# TSAL_logic_TNN_V1_0.net
KiCad netlist of a schematic drawn in EAGLE
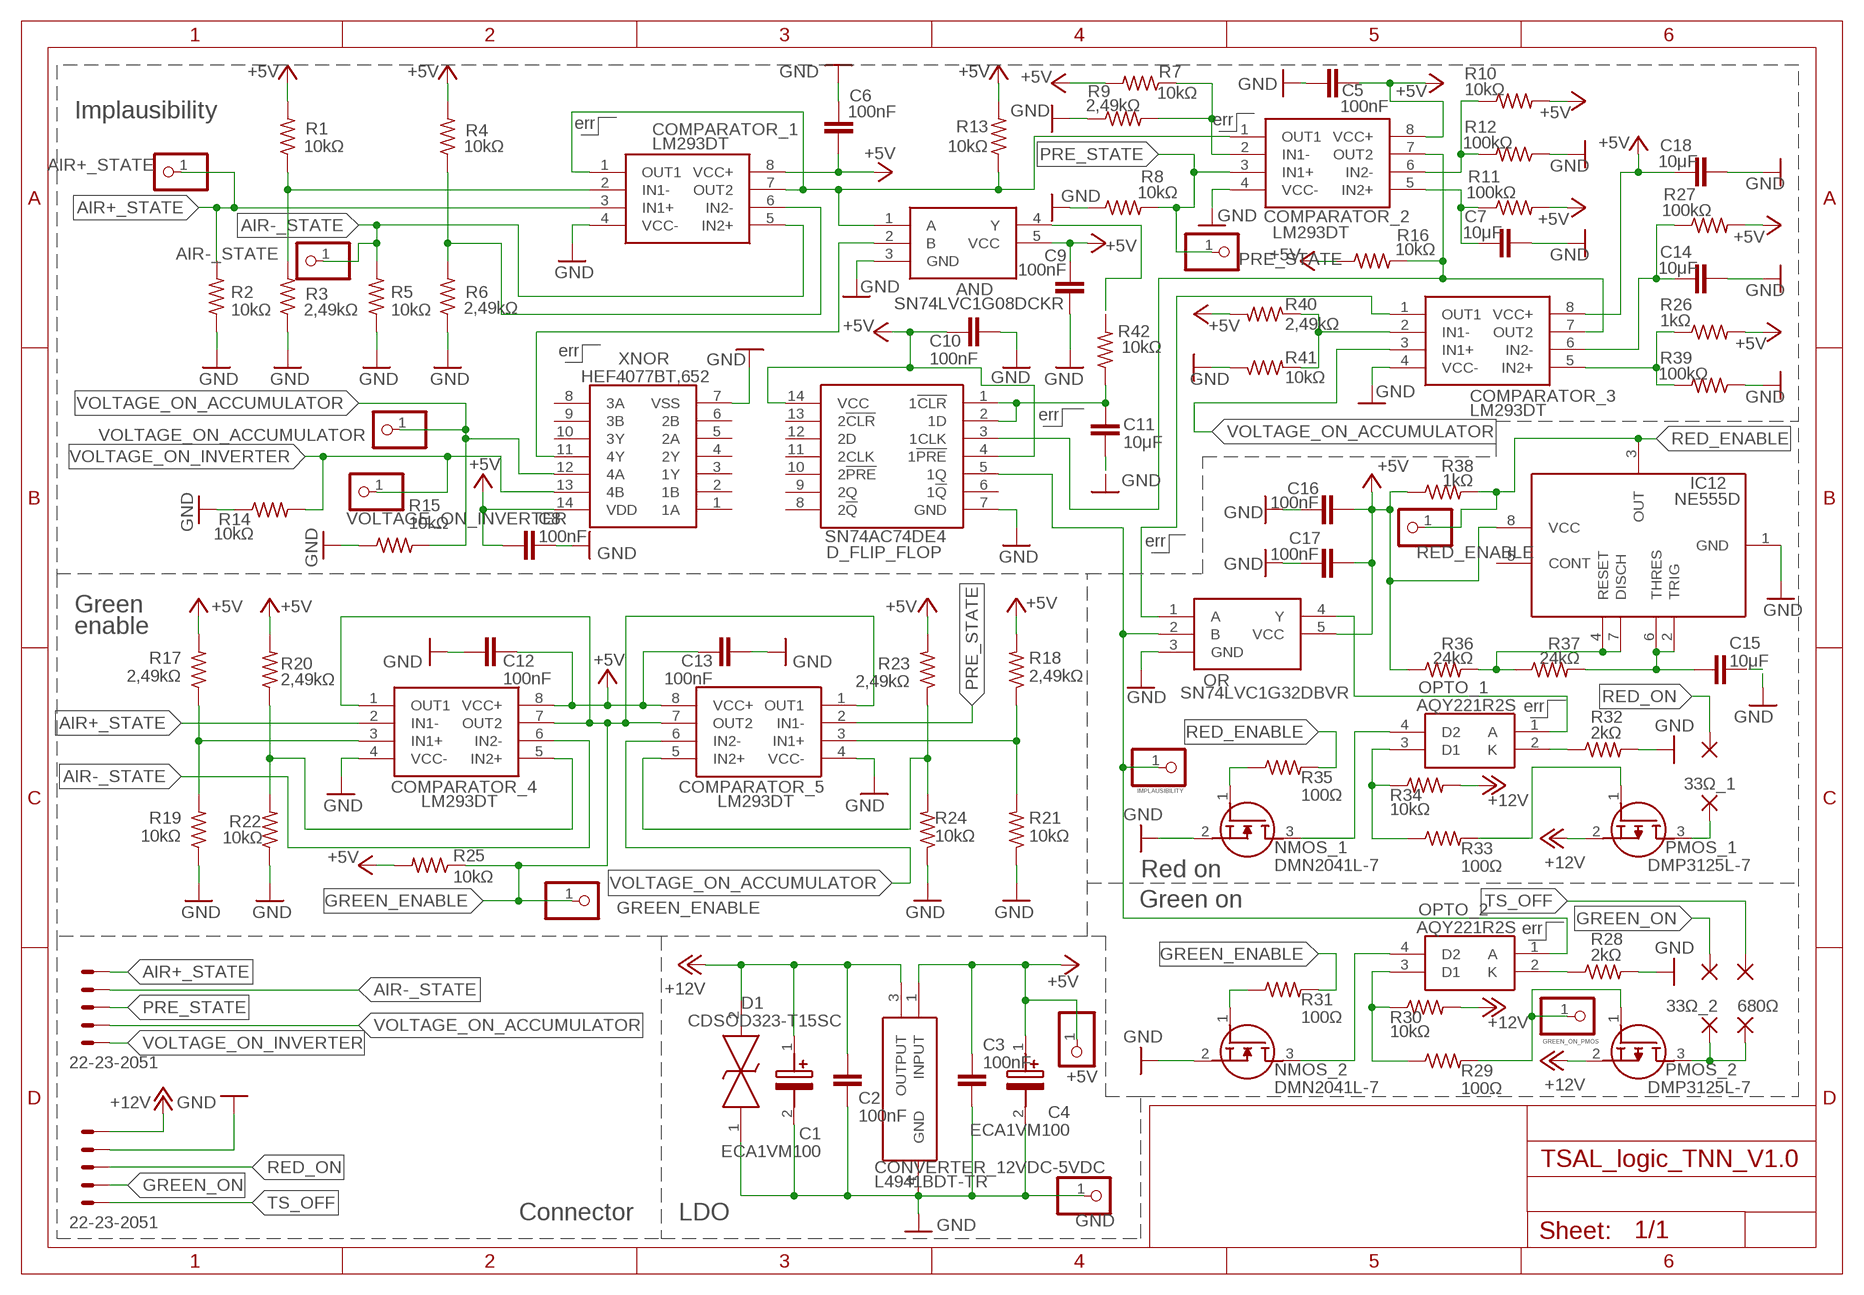
[diagram p0: schematic, sheet 1]

(export (version "E")
  (design (tool "Eeschema 10.0.6"))
  (components
    (comp (ref "+5V")
      (value "PINHD-1X1")
      (footprint "eagle-import:1X01")
      (libsource (lib "eagle-import") (part "PINHD-1X1"))
    )
    (comp (ref "33Ω_1")
      (value "1,6/0,8")
      (footprint "eagle-import:1,6_0,8")
      (libsource (lib "eagle-import") (part "1,6/0,8"))
    )
    (comp (ref "33Ω_1_")
      (value "1,6/0,8")
      (footprint "eagle-import:1,6_0,8")
      (libsource (lib "eagle-import") (part "1,6/0,8"))
    )
    (comp (ref "33Ω_2")
      (value "1,6/0,8")
      (footprint "eagle-import:1,6_0,8")
      (libsource (lib "eagle-import") (part "1,6/0,8"))
    )
    (comp (ref "33Ω_2_")
      (value "1,6/0,8")
      (footprint "eagle-import:1,6_0,8")
      (libsource (lib "eagle-import") (part "1,6/0,8"))
    )
    (comp (ref "680Ω")
      (value "1,6/0,8")
      (footprint "eagle-import:1,6_0,8")
      (libsource (lib "eagle-import") (part "1,6/0,8"))
    )
    (comp (ref "680Ω_")
      (value "1,6/0,8")
      (footprint "eagle-import:1,6_0,8")
      (libsource (lib "eagle-import") (part "1,6/0,8"))
    )
    (comp (ref "AIR+_STATE")
      (value "PINHD-1X1")
      (footprint "eagle-import:1X01")
      (libsource (lib "eagle-import") (part "PINHD-1X1"))
    )
    (comp (ref "AIR-_STATE")
      (value "PINHD-1X1")
      (footprint "eagle-import:1X01")
      (libsource (lib "eagle-import") (part "PINHD-1X1"))
    )
    (comp (ref "AND")
      (value "SN74LVC1G08DCKR")
      (footprint "eagle-import:SOT65P210X110-5N")
      (fields (field (name "MOUSER_PART_NUMBER") "595-SN74LVC1G08DCKR"))
      (libsource (lib "eagle-import") (part "SN74LVC1G08DCKR"))
    )
    (comp (ref "C1")
      (value "ECA1VM100")
      (footprint "eagle-import:CAPPRD200W55D525H1200")
      (libsource (lib "eagle-import") (part "ECA1VM100"))
    )
    (comp (ref "C2")
      (value "100nF")
      (footprint "eagle-import:C0603")
      (libsource (lib "eagle-import") (part "C-EUC0603"))
    )
    (comp (ref "C3")
      (value "100nF")
      (footprint "eagle-import:C0603")
      (libsource (lib "eagle-import") (part "C-EUC0603"))
    )
    (comp (ref "C4")
      (value "ECA1VM100")
      (footprint "eagle-import:CAPPRD200W55D525H1200")
      (libsource (lib "eagle-import") (part "ECA1VM100"))
    )
    (comp (ref "C5")
      (value "100nF")
      (footprint "eagle-import:C0603")
      (libsource (lib "eagle-import") (part "C-EUC0603"))
    )
    (comp (ref "C6")
      (value "100nF")
      (footprint "eagle-import:C0603")
      (libsource (lib "eagle-import") (part "C-EUC0603"))
    )
    (comp (ref "C7")
      (value "10μF")
      (footprint "eagle-import:C0603")
      (libsource (lib "eagle-import") (part "C-EUC0603"))
    )
    (comp (ref "C8")
      (value "100nF")
      (footprint "eagle-import:C0603")
      (libsource (lib "eagle-import") (part "C-EUC0603"))
    )
    (comp (ref "C9")
      (value "100nF")
      (footprint "eagle-import:C0603")
      (libsource (lib "eagle-import") (part "C-EUC0603"))
    )
    (comp (ref "C10")
      (value "100nF")
      (footprint "eagle-import:C0603")
      (libsource (lib "eagle-import") (part "C-EUC0603"))
    )
    (comp (ref "C11")
      (value "10μF")
      (footprint "eagle-import:C0603")
      (libsource (lib "eagle-import") (part "C-EUC0603"))
    )
    (comp (ref "C12")
      (value "100nF")
      (footprint "eagle-import:C0603")
      (libsource (lib "eagle-import") (part "C-EUC0603"))
    )
    (comp (ref "C13")
      (value "100nF")
      (footprint "eagle-import:C0603")
      (libsource (lib "eagle-import") (part "C-EUC0603"))
    )
    (comp (ref "C14")
      (value "10μF")
      (footprint "eagle-import:C0603")
      (libsource (lib "eagle-import") (part "C-EUC0603"))
    )
    (comp (ref "C15")
      (value "10μF")
      (footprint "eagle-import:C0603")
      (libsource (lib "eagle-import") (part "C-EUC0603"))
    )
    (comp (ref "C16")
      (value "100nF")
      (footprint "eagle-import:C0603")
      (libsource (lib "eagle-import") (part "C-EUC0603"))
    )
    (comp (ref "C17")
      (value "100nF")
      (footprint "eagle-import:C0603")
      (libsource (lib "eagle-import") (part "C-EUC0603"))
    )
    (comp (ref "C18")
      (value "10μF")
      (footprint "eagle-import:C0603")
      (libsource (lib "eagle-import") (part "C-EUC0603"))
    )
    (comp (ref "COMPARATOR_1")
      (value "LM293DT")
      (footprint "eagle-import:SOIC127P600X175-8N")
      (fields (field (name "MOUSER_PART_NUMBER") "511-LM293DT"))
      (libsource (lib "eagle-import") (part "LM293DT"))
    )
    (comp (ref "COMPARATOR_2")
      (value "LM293DT")
      (footprint "eagle-import:SOIC127P600X175-8N")
      (fields (field (name "MOUSER_PART_NUMBER") "511-LM293DT"))
      (libsource (lib "eagle-import") (part "LM293DT"))
    )
    (comp (ref "COMPARATOR_3")
      (value "LM293DT")
      (footprint "eagle-import:SOIC127P600X175-8N")
      (fields (field (name "MOUSER_PART_NUMBER") "511-LM293DT"))
      (libsource (lib "eagle-import") (part "LM293DT"))
    )
    (comp (ref "COMPARATOR_4")
      (value "LM293DT")
      (footprint "eagle-import:SOIC127P600X175-8N")
      (fields (field (name "MOUSER_PART_NUMBER") "511-LM293DT"))
      (libsource (lib "eagle-import") (part "LM293DT"))
    )
    (comp (ref "COMPARATOR_5")
      (value "LM293DT")
      (footprint "eagle-import:SOIC127P600X175-8N")
      (fields (field (name "MOUSER_PART_NUMBER") "511-LM293DT"))
      (libsource (lib "eagle-import") (part "LM293DT"))
    )
    (comp (ref "CONTACTOR_STATE_AND_VOLTAGE_MEASUREMENT")
      (value "22-23-2051")
      (footprint "eagle-import:22-23-2051")
      (fields (field (name "MF") "MOLEX"))
      (libsource (lib "eagle-import") (part "22-23-2051"))
    )
    (comp (ref "CONVERTER_12VDC-5VDC")
      (value "L4941BDT-TR")
      (footprint "eagle-import:TO228P972X240-3N")
      (fields (field (name "MOUSER_PART_NUMBER") "511-L4941BDT-TR"))
      (libsource (lib "eagle-import") (part "L4941BDT-TR"))
    )
    (comp (ref "D1")
      (value "CDSOD323-T15SC")
      (footprint "eagle-import:SOD-323")
      (fields (field (name "MOUSER_PART_NUMBER") "652-CDSOD323-T15SC"))
      (libsource (lib "eagle-import") (part "CDSOD323-T15SC"))
    )
    (comp (ref "D_FLIP_FLOP")
      (value "SN74AC74DE4")
      (footprint "eagle-import:SOIC127P600X175-14N")
      (fields (field (name "MOUSER_PART_NUMBER") "595-SN74AC74DE4"))
      (libsource (lib "eagle-import") (part "SN74AC74DE4"))
    )
    (comp (ref "GND")
      (value "PINHD-1X1")
      (footprint "eagle-import:1X01")
      (libsource (lib "eagle-import") (part "PINHD-1X1"))
    )
    (comp (ref "GREEN_ENABLE")
      (value "PINHD-1X1")
      (footprint "eagle-import:1X01")
      (libsource (lib "eagle-import") (part "PINHD-1X1"))
    )
    (comp (ref "GREEN_ON_PMOS")
      (value "PINHD-1X1")
      (footprint "eagle-import:1X01")
      (libsource (lib "eagle-import") (part "PINHD-1X1"))
    )
    (comp (ref "IC12")
      (value "NE555D")
      (footprint "eagle-import:SOIC127P600X175-8N")
      (fields (field (name "MOUSER_PART_NUMBER") "595-NE555D"))
      (libsource (lib "eagle-import") (part "NE555D"))
    )
    (comp (ref "IMPLAUSIBILITY")
      (value "PINHD-1X1")
      (footprint "eagle-import:1X01")
      (libsource (lib "eagle-import") (part "PINHD-1X1"))
    )
    (comp (ref "NMOS_1")
      (value "DMN2041L-7")
      (footprint "eagle-import:SOT96P240X110-3N")
      (fields (field (name "MOUSER_PART_NUMBER") "621-DMN2041L-7"))
      (libsource (lib "eagle-import") (part "DMN2041L-7"))
    )
    (comp (ref "NMOS_2")
      (value "DMN2041L-7")
      (footprint "eagle-import:SOT96P240X110-3N")
      (fields (field (name "MOUSER_PART_NUMBER") "621-DMN2041L-7"))
      (libsource (lib "eagle-import") (part "DMN2041L-7"))
    )
    (comp (ref "OPTO_1")
      (value "AQY221R2S")
      (footprint "eagle-import:SOP254P680X230-4N")
      (fields (field (name "MOUSER_PART_NUMBER") "769-AQY221R2S"))
      (libsource (lib "eagle-import") (part "AQY221R2S"))
    )
    (comp (ref "OPTO_2")
      (value "AQY221R2S")
      (footprint "eagle-import:SOP254P680X230-4N")
      (fields (field (name "MOUSER_PART_NUMBER") "769-AQY221R2S"))
      (libsource (lib "eagle-import") (part "AQY221R2S"))
    )
    (comp (ref "OR")
      (value "SN74LVC1G32DBVR")
      (footprint "eagle-import:SOT95P280X145-5N")
      (fields (field (name "MOUSER_PART_NUMBER") "595-SN74LVC1G32DBVR"))
      (libsource (lib "eagle-import") (part "SN74LVC1G32DBVR"))
    )
    (comp (ref "PMOS_1")
      (value "DMP3125L-7")
      (footprint "eagle-import:SOT96P240X110-3N")
      (fields (field (name "MOUSER_PART_NUMBER") "621-DMP3125L-7"))
      (libsource (lib "eagle-import") (part "DMP3125L-7"))
    )
    (comp (ref "PMOS_2")
      (value "DMP3125L-7")
      (footprint "eagle-import:SOT96P240X110-3N")
      (fields (field (name "MOUSER_PART_NUMBER") "621-DMP3125L-7"))
      (libsource (lib "eagle-import") (part "DMP3125L-7"))
    )
    (comp (ref "PRE_STATE")
      (value "PINHD-1X1")
      (footprint "eagle-import:1X01")
      (libsource (lib "eagle-import") (part "PINHD-1X1"))
    )
    (comp (ref "R1")
      (value "10kΩ")
      (footprint "eagle-import:R0603")
      (libsource (lib "eagle-import") (part "R-US_R0603"))
    )
    (comp (ref "R2")
      (value "10kΩ")
      (footprint "eagle-import:R0603")
      (libsource (lib "eagle-import") (part "R-US_R0603"))
    )
    (comp (ref "R3")
      (value "2,49kΩ")
      (footprint "eagle-import:R0603")
      (libsource (lib "eagle-import") (part "R-US_R0603"))
    )
    (comp (ref "R4")
      (value "10kΩ")
      (footprint "eagle-import:R0603")
      (libsource (lib "eagle-import") (part "R-US_R0603"))
    )
    (comp (ref "R5")
      (value "10kΩ")
      (footprint "eagle-import:R0603")
      (libsource (lib "eagle-import") (part "R-US_R0603"))
    )
    (comp (ref "R6")
      (value "2,49kΩ")
      (footprint "eagle-import:R0603")
      (libsource (lib "eagle-import") (part "R-US_R0603"))
    )
    (comp (ref "R7")
      (value "10kΩ")
      (footprint "eagle-import:R0603")
      (libsource (lib "eagle-import") (part "R-US_R0603"))
    )
    (comp (ref "R8")
      (value "10kΩ")
      (footprint "eagle-import:R0603")
      (libsource (lib "eagle-import") (part "R-US_R0603"))
    )
    (comp (ref "R9")
      (value "2,49kΩ")
      (footprint "eagle-import:R0603")
      (libsource (lib "eagle-import") (part "R-US_R0603"))
    )
    (comp (ref "R10")
      (value "10kΩ")
      (footprint "eagle-import:R0603")
      (libsource (lib "eagle-import") (part "R-US_R0603"))
    )
    (comp (ref "R11")
      (value "100kΩ")
      (footprint "eagle-import:R0603")
      (libsource (lib "eagle-import") (part "R-US_R0603"))
    )
    (comp (ref "R12")
      (value "100kΩ")
      (footprint "eagle-import:R0603")
      (libsource (lib "eagle-import") (part "R-US_R0603"))
    )
    (comp (ref "R13")
      (value "10kΩ")
      (footprint "eagle-import:R0603")
      (libsource (lib "eagle-import") (part "R-US_R0603"))
    )
    (comp (ref "R14")
      (value "10kΩ")
      (footprint "eagle-import:R0603")
      (libsource (lib "eagle-import") (part "R-US_R0603"))
    )
    (comp (ref "R15")
      (value "10kΩ")
      (footprint "eagle-import:R0603")
      (libsource (lib "eagle-import") (part "R-US_R0603"))
    )
    (comp (ref "R16")
      (value "10kΩ")
      (footprint "eagle-import:R0603")
      (libsource (lib "eagle-import") (part "R-US_R0603"))
    )
    (comp (ref "R17")
      (value "2,49kΩ")
      (footprint "eagle-import:R0603")
      (libsource (lib "eagle-import") (part "R-US_R0603"))
    )
    (comp (ref "R18")
      (value "2,49kΩ")
      (footprint "eagle-import:R0603")
      (libsource (lib "eagle-import") (part "R-US_R0603"))
    )
    (comp (ref "R19")
      (value "10kΩ")
      (footprint "eagle-import:R0603")
      (libsource (lib "eagle-import") (part "R-US_R0603"))
    )
    (comp (ref "R20")
      (value "2,49kΩ")
      (footprint "eagle-import:R0603")
      (libsource (lib "eagle-import") (part "R-US_R0603"))
    )
    (comp (ref "R21")
      (value "10kΩ")
      (footprint "eagle-import:R0603")
      (libsource (lib "eagle-import") (part "R-US_R0603"))
    )
    (comp (ref "R22")
      (value "10kΩ")
      (footprint "eagle-import:R0603")
      (libsource (lib "eagle-import") (part "R-US_R0603"))
    )
    (comp (ref "R23")
      (value "2,49kΩ")
      (footprint "eagle-import:R0603")
      (libsource (lib "eagle-import") (part "R-US_R0603"))
    )
    (comp (ref "R24")
      (value "10kΩ")
      (footprint "eagle-import:R0603")
      (libsource (lib "eagle-import") (part "R-US_R0603"))
    )
    (comp (ref "R25")
      (value "10kΩ")
      (footprint "eagle-import:R0603")
      (libsource (lib "eagle-import") (part "R-US_R0603"))
    )
    (comp (ref "R26")
      (value "1kΩ")
      (footprint "eagle-import:R0603")
      (libsource (lib "eagle-import") (part "R-US_R0603"))
    )
    (comp (ref "R27")
      (value "100kΩ")
      (footprint "eagle-import:R0603")
      (libsource (lib "eagle-import") (part "R-US_R0603"))
    )
    (comp (ref "R28")
      (value "2kΩ")
      (footprint "eagle-import:R0603")
      (libsource (lib "eagle-import") (part "R-US_R0603"))
    )
    (comp (ref "R29")
      (value "100Ω")
      (footprint "eagle-import:R0603")
      (libsource (lib "eagle-import") (part "R-US_R0603"))
    )
    (comp (ref "R30")
      (value "10kΩ")
      (footprint "eagle-import:R0603")
      (libsource (lib "eagle-import") (part "R-US_R0603"))
    )
    (comp (ref "R31")
      (value "100Ω")
      (footprint "eagle-import:R0603")
      (libsource (lib "eagle-import") (part "R-US_R0603"))
    )
    (comp (ref "R32")
      (value "2kΩ")
      (footprint "eagle-import:R0603")
      (libsource (lib "eagle-import") (part "R-US_R0603"))
    )
    (comp (ref "R33")
      (value "100Ω")
      (footprint "eagle-import:R0603")
      (libsource (lib "eagle-import") (part "R-US_R0603"))
    )
    (comp (ref "R34")
      (value "10kΩ")
      (footprint "eagle-import:R0603")
      (libsource (lib "eagle-import") (part "R-US_R0603"))
    )
    (comp (ref "R35")
      (value "100Ω")
      (footprint "eagle-import:R0603")
      (libsource (lib "eagle-import") (part "R-US_R0603"))
    )
    (comp (ref "R36")
      (value "24kΩ")
      (footprint "eagle-import:R0603")
      (libsource (lib "eagle-import") (part "R-US_R0603"))
    )
    (comp (ref "R37")
      (value "24kΩ")
      (footprint "eagle-import:R0603")
      (libsource (lib "eagle-import") (part "R-US_R0603"))
    )
    (comp (ref "R38")
      (value "1kΩ")
      (footprint "eagle-import:R0603")
      (libsource (lib "eagle-import") (part "R-US_R0603"))
    )
    (comp (ref "R39")
      (value "100kΩ")
      (footprint "eagle-import:R0603")
      (libsource (lib "eagle-import") (part "R-US_R0603"))
    )
    (comp (ref "R40")
      (value "2,49kΩ")
      (footprint "eagle-import:R0603")
      (libsource (lib "eagle-import") (part "R-US_R0603"))
    )
    (comp (ref "R41")
      (value "10kΩ")
      (footprint "eagle-import:R0603")
      (libsource (lib "eagle-import") (part "R-US_R0603"))
    )
    (comp (ref "R42")
      (value "10kΩ")
      (footprint "eagle-import:R0603")
      (libsource (lib "eagle-import") (part "R-US_R0603"))
    )
    (comp (ref "RED_ENABLE")
      (value "PINHD-1X1")
      (footprint "eagle-import:1X01")
      (libsource (lib "eagle-import") (part "PINHD-1X1"))
    )
    (comp (ref "TSAL_LED_AND_POWER")
      (value "22-23-2051")
      (footprint "eagle-import:22-23-2051")
      (fields (field (name "MF") "MOLEX"))
      (libsource (lib "eagle-import") (part "22-23-2051"))
    )
    (comp (ref "VOLTAGE_ON_ACCUMULATOR")
      (value "PINHD-1X1")
      (footprint "eagle-import:1X01")
      (libsource (lib "eagle-import") (part "PINHD-1X1"))
    )
    (comp (ref "VOLTAGE_ON_INVERTER")
      (value "PINHD-1X1")
      (footprint "eagle-import:1X01")
      (libsource (lib "eagle-import") (part "PINHD-1X1"))
    )
    (comp (ref "XNOR")
      (value "HEF4077BT,652")
      (footprint "eagle-import:SOIC127P600X175-14N")
      (fields (field (name "MOUSER_PART_NUMBER") "771-HEF4077BTD"))
      (libsource (lib "eagle-import") (part "HEF4077BT,652"))
    )
  )
  (nets
    (net (code "1") (name "+5V") (class "Default")
      (node (ref "+5V") (pin "1") (pinfunction "1_1") (pintype "passive"))
      (node (ref "AND") (pin "5") (pinfunction "VCC_5") (pintype "bidirectional"))
      (node (ref "C10") (pin "1") (pinfunction "1_1") (pintype "passive"))
      (node (ref "C12") (pin "1") (pinfunction "1_1") (pintype "passive"))
      (node (ref "C13") (pin "1") (pinfunction "1_1") (pintype "passive"))
      (node (ref "C16") (pin "1") (pinfunction "1_1") (pintype "passive"))
      (node (ref "C17") (pin "1") (pinfunction "1_1") (pintype "passive"))
      (node (ref "C18") (pin "1") (pinfunction "1_1") (pintype "passive"))
      (node (ref "C3") (pin "1") (pinfunction "1_1") (pintype "passive"))
      (node (ref "C4") (pin "1") (pinfunction "+_1") (pintype "bidirectional"))
      (node (ref "C5") (pin "2") (pinfunction "2_2") (pintype "passive"))
      (node (ref "C6") (pin "2") (pinfunction "2_2") (pintype "passive"))
      (node (ref "C8") (pin "1") (pinfunction "1_1") (pintype "passive"))
      (node (ref "C9") (pin "1") (pinfunction "1_1") (pintype "passive"))
      (node (ref "COMPARATOR_1") (pin "8") (pinfunction "VCC+_8") (pintype "bidirectional"))
      (node (ref "COMPARATOR_2") (pin "8") (pinfunction "VCC+_8") (pintype "bidirectional"))
      (node (ref "COMPARATOR_3") (pin "8") (pinfunction "VCC+_8") (pintype "bidirectional"))
      (node (ref "COMPARATOR_4") (pin "8") (pinfunction "VCC+_8") (pintype "bidirectional"))
      (node (ref "COMPARATOR_5") (pin "8") (pinfunction "VCC+_8") (pintype "bidirectional"))
      (node (ref "CONVERTER_12VDC-5VDC") (pin "1") (pinfunction "INPUT_1") (pintype "output"))
      (node (ref "D_FLIP_FLOP") (pin "14") (pinfunction "VCC_14") (pintype "bidirectional"))
      (node (ref "D_FLIP_FLOP") (pin "4") (pinfunction "1~{PRE}_4") (pintype "bidirectional"))
      (node (ref "IC12") (pin "8") (pinfunction "VCC_8") (pintype "bidirectional"))
      (node (ref "OR") (pin "5") (pinfunction "VCC_5") (pintype "bidirectional"))
      (node (ref "R1") (pin "2") (pinfunction "2_2") (pintype "passive"))
      (node (ref "R10") (pin "2") (pinfunction "2_2") (pintype "passive"))
      (node (ref "R11") (pin "2") (pinfunction "2_2") (pintype "passive"))
      (node (ref "R13") (pin "2") (pinfunction "2_2") (pintype "passive"))
      (node (ref "R16") (pin "1") (pinfunction "1_1") (pintype "passive"))
      (node (ref "R17") (pin "2") (pinfunction "2_2") (pintype "passive"))
      (node (ref "R18") (pin "2") (pinfunction "2_2") (pintype "passive"))
      (node (ref "R20") (pin "2") (pinfunction "2_2") (pintype "passive"))
      (node (ref "R23") (pin "2") (pinfunction "2_2") (pintype "passive"))
      (node (ref "R25") (pin "2") (pinfunction "2_2") (pintype "passive"))
      (node (ref "R26") (pin "2") (pinfunction "2_2") (pintype "passive"))
      (node (ref "R27") (pin "2") (pinfunction "2_2") (pintype "passive"))
      (node (ref "R36") (pin "1") (pinfunction "1_1") (pintype "passive"))
      (node (ref "R38") (pin "1") (pinfunction "1_1") (pintype "passive"))
      (node (ref "R4") (pin "2") (pinfunction "2_2") (pintype "passive"))
      (node (ref "R40") (pin "2") (pinfunction "2_2") (pintype "passive"))
      (node (ref "R7") (pin "2") (pinfunction "2_2") (pintype "passive"))
      (node (ref "XNOR") (pin "14") (pinfunction "VDD_14") (pintype "bidirectional"))
    )
    (net (code "2") (name "+12V") (class "Default")
      (node (ref "C1") (pin "1") (pinfunction "+_1") (pintype "bidirectional"))
      (node (ref "C2") (pin "1") (pinfunction "1_1") (pintype "passive"))
      (node (ref "CONVERTER_12VDC-5VDC") (pin "3") (pinfunction "OUTPUT_3") (pintype "power_in"))
      (node (ref "D1") (pin "2") (pinfunction "2_2") (pintype "bidirectional"))
      (node (ref "PMOS_1") (pin "2") (pinfunction "S_2") (pintype "bidirectional"))
      (node (ref "PMOS_2") (pin "2") (pinfunction "S_2") (pintype "bidirectional"))
      (node (ref "R30") (pin "2") (pinfunction "2_2") (pintype "passive"))
      (node (ref "R34") (pin "2") (pinfunction "2_2") (pintype "passive"))
      (node (ref "TSAL_LED_AND_POWER") (pin "5") (pinfunction "S_5") (pintype "passive"))
    )
    (net (code "3") (name "AIR+_STATE") (class "Default")
      (node (ref "AIR+_STATE") (pin "1") (pinfunction "1_1") (pintype "passive"))
      (node (ref "COMPARATOR_1") (pin "3") (pinfunction "IN1+_3") (pintype "bidirectional"))
      (node (ref "COMPARATOR_4") (pin "2") (pinfunction "IN1-_2") (pintype "bidirectional"))
      (node (ref "CONTACTOR_STATE_AND_VOLTAGE_MEASUREMENT") (pin "5") (pinfunction "S_5") (pintype "passive"))
      (node (ref "R2") (pin "2") (pinfunction "2_2") (pintype "passive"))
    )
    (net (code "4") (name "AIR-_STATE") (class "Default")
      (node (ref "AIR-_STATE") (pin "1") (pinfunction "1_1") (pintype "passive"))
      (node (ref "COMPARATOR_1") (pin "5") (pinfunction "IN2+_5") (pintype "bidirectional"))
      (node (ref "COMPARATOR_4") (pin "6") (pinfunction "IN2-_6") (pintype "bidirectional"))
      (node (ref "CONTACTOR_STATE_AND_VOLTAGE_MEASUREMENT") (pin "4") (pinfunction "S_4") (pintype "passive"))
      (node (ref "R5") (pin "2") (pinfunction "2_2") (pintype "passive"))
    )
    (net (code "5") (name "GND") (class "Default")
      (node (ref "AND") (pin "3") (pinfunction "GND_3") (pintype "bidirectional"))
      (node (ref "C1") (pin "2") (pinfunction "-_2") (pintype "bidirectional"))
      (node (ref "C10") (pin "2") (pinfunction "2_2") (pintype "passive"))
      (node (ref "C11") (pin "2") (pinfunction "2_2") (pintype "passive"))
      (node (ref "C12") (pin "2") (pinfunction "2_2") (pintype "passive"))
      (node (ref "C13") (pin "2") (pinfunction "2_2") (pintype "passive"))
      (node (ref "C14") (pin "2") (pinfunction "2_2") (pintype "passive"))
      (node (ref "C15") (pin "2") (pinfunction "2_2") (pintype "passive"))
      (node (ref "C16") (pin "2") (pinfunction "2_2") (pintype "passive"))
      (node (ref "C17") (pin "2") (pinfunction "2_2") (pintype "passive"))
      (node (ref "C18") (pin "2") (pinfunction "2_2") (pintype "passive"))
      (node (ref "C2") (pin "2") (pinfunction "2_2") (pintype "passive"))
      (node (ref "C3") (pin "2") (pinfunction "2_2") (pintype "passive"))
      (node (ref "C4") (pin "2") (pinfunction "-_2") (pintype "bidirectional"))
      (node (ref "C5") (pin "1") (pinfunction "1_1") (pintype "passive"))
      (node (ref "C6") (pin "1") (pinfunction "1_1") (pintype "passive"))
      (node (ref "C7") (pin "2") (pinfunction "2_2") (pintype "passive"))
      (node (ref "C8") (pin "2") (pinfunction "2_2") (pintype "passive"))
      (node (ref "C9") (pin "2") (pinfunction "2_2") (pintype "passive"))
      (node (ref "COMPARATOR_1") (pin "4") (pinfunction "VCC-_4") (pintype "bidirectional"))
      (node (ref "COMPARATOR_2") (pin "4") (pinfunction "VCC-_4") (pintype "bidirectional"))
      (node (ref "COMPARATOR_3") (pin "4") (pinfunction "VCC-_4") (pintype "bidirectional"))
      (node (ref "COMPARATOR_4") (pin "4") (pinfunction "VCC-_4") (pintype "bidirectional"))
      (node (ref "COMPARATOR_5") (pin "4") (pinfunction "VCC-_4") (pintype "bidirectional"))
      (node (ref "CONVERTER_12VDC-5VDC") (pin "4") (pinfunction "GND_4") (pintype "input"))
      (node (ref "D1") (pin "1") (pinfunction "1_1") (pintype "bidirectional"))
      (node (ref "D_FLIP_FLOP") (pin "7") (pinfunction "GND_7") (pintype "bidirectional"))
      (node (ref "GND") (pin "1") (pinfunction "1_1") (pintype "passive"))
      (node (ref "IC12") (pin "1") (pinfunction "GND_1") (pintype "bidirectional"))
      (node (ref "NMOS_1") (pin "2") (pinfunction "S_2") (pintype "bidirectional"))
      (node (ref "NMOS_2") (pin "2") (pinfunction "S_2") (pintype "bidirectional"))
      (node (ref "OR") (pin "3") (pinfunction "GND_3") (pintype "bidirectional"))
      (node (ref "R12") (pin "1") (pinfunction "1_1") (pintype "passive"))
      (node (ref "R14") (pin "1") (pinfunction "1_1") (pintype "passive"))
      (node (ref "R15") (pin "1") (pinfunction "1_1") (pintype "passive"))
      (node (ref "R19") (pin "1") (pinfunction "1_1") (pintype "passive"))
      (node (ref "R2") (pin "1") (pinfunction "1_1") (pintype "passive"))
      (node (ref "R21") (pin "1") (pinfunction "1_1") (pintype "passive"))
      (node (ref "R22") (pin "1") (pinfunction "1_1") (pintype "passive"))
      (node (ref "R24") (pin "1") (pinfunction "1_1") (pintype "passive"))
      (node (ref "R28") (pin "2") (pinfunction "2_2") (pintype "passive"))
      (node (ref "R3") (pin "1") (pinfunction "1_1") (pintype "passive"))
      (node (ref "R32") (pin "2") (pinfunction "2_2") (pintype "passive"))
      (node (ref "R39") (pin "1") (pinfunction "1_1") (pintype "passive"))
      (node (ref "R41") (pin "1") (pinfunction "1_1") (pintype "passive"))
      (node (ref "R5") (pin "1") (pinfunction "1_1") (pintype "passive"))
      (node (ref "R6") (pin "1") (pinfunction "1_1") (pintype "passive"))
      (node (ref "R8") (pin "1") (pinfunction "1_1") (pintype "passive"))
      (node (ref "R9") (pin "1") (pinfunction "1_1") (pintype "passive"))
      (node (ref "TSAL_LED_AND_POWER") (pin "4") (pinfunction "S_4") (pintype "passive"))
      (node (ref "XNOR") (pin "7") (pinfunction "VSS_7") (pintype "bidirectional"))
    )
    (net (code "6") (name "GREEN_ENABLE") (class "Default")
      (node (ref "COMPARATOR_4") (pin "1") (pinfunction "OUT1_1") (pintype "bidirectional"))
      (node (ref "COMPARATOR_4") (pin "7") (pinfunction "OUT2_7") (pintype "bidirectional"))
      (node (ref "COMPARATOR_5") (pin "1") (pinfunction "OUT1_1") (pintype "bidirectional"))
      (node (ref "COMPARATOR_5") (pin "7") (pinfunction "OUT2_7") (pintype "bidirectional"))
      (node (ref "GREEN_ENABLE") (pin "1") (pinfunction "1_1") (pintype "passive"))
      (node (ref "R25") (pin "1") (pinfunction "1_1") (pintype "passive"))
      (node (ref "R31") (pin "2") (pinfunction "2_2") (pintype "passive"))
    )
    (net (code "7") (name "GREEN_ON") (class "Default")
      (node (ref "33Ω_2_") (pin "1") (pinfunction "P_1") (pintype "passive"))
      (node (ref "TSAL_LED_AND_POWER") (pin "2") (pinfunction "S_2") (pintype "passive"))
    )
    (net (code "8") (name "Net-(33Ω_1-P)") (class "Default")
      (node (ref "33Ω_1") (pin "1") (pinfunction "P_1") (pintype "passive"))
      (node (ref "PMOS_1") (pin "3") (pinfunction "D_3") (pintype "bidirectional"))
    )
    (net (code "9") (name "Net-(33Ω_2-P)") (class "Default")
      (node (ref "33Ω_2") (pin "1") (pinfunction "P_1") (pintype "passive"))
      (node (ref "680Ω") (pin "1") (pinfunction "P_1") (pintype "passive"))
      (node (ref "PMOS_2") (pin "3") (pinfunction "D_3") (pintype "bidirectional"))
    )
    (net (code "10") (name "Net-(AND-A)") (class "Default")
      (node (ref "AND") (pin "1") (pinfunction "A_1") (pintype "bidirectional"))
      (node (ref "COMPARATOR_1") (pin "1") (pinfunction "OUT1_1") (pintype "bidirectional"))
      (node (ref "COMPARATOR_1") (pin "7") (pinfunction "OUT2_7") (pintype "bidirectional"))
      (node (ref "COMPARATOR_2") (pin "1") (pinfunction "OUT1_1") (pintype "bidirectional"))
      (node (ref "R13") (pin "1") (pinfunction "1_1") (pintype "passive"))
    )
    (net (code "11") (name "Net-(AND-B)") (class "Default")
      (node (ref "AND") (pin "2") (pinfunction "B_2") (pintype "bidirectional"))
      (node (ref "XNOR") (pin "11") (pinfunction "4Y_11") (pintype "bidirectional"))
    )
    (net (code "12") (name "Net-(AND-Y)") (class "Default")
      (node (ref "AND") (pin "4") (pinfunction "Y_4") (pintype "bidirectional"))
      (node (ref "R42") (pin "2") (pinfunction "2_2") (pintype "passive"))
    )
    (net (code "13") (name "Net-(COMPARATOR_1-IN1-)") (class "Default")
      (node (ref "COMPARATOR_1") (pin "2") (pinfunction "IN1-_2") (pintype "bidirectional"))
      (node (ref "R1") (pin "1") (pinfunction "1_1") (pintype "passive"))
      (node (ref "R3") (pin "2") (pinfunction "2_2") (pintype "passive"))
    )
    (net (code "14") (name "Net-(COMPARATOR_1-IN2-)") (class "Default")
      (node (ref "COMPARATOR_1") (pin "6") (pinfunction "IN2-_6") (pintype "bidirectional"))
      (node (ref "R4") (pin "1") (pinfunction "1_1") (pintype "passive"))
      (node (ref "R6") (pin "2") (pinfunction "2_2") (pintype "passive"))
    )
    (net (code "15") (name "Net-(COMPARATOR_2-IN1-)") (class "Default")
      (node (ref "COMPARATOR_2") (pin "2") (pinfunction "IN1-_2") (pintype "bidirectional"))
      (node (ref "R7") (pin "1") (pinfunction "1_1") (pintype "passive"))
      (node (ref "R9") (pin "2") (pinfunction "2_2") (pintype "passive"))
    )
    (net (code "16") (name "Net-(COMPARATOR_2-IN2+)") (class "Default")
      (node (ref "C7") (pin "1") (pinfunction "1_1") (pintype "passive"))
      (node (ref "COMPARATOR_2") (pin "5") (pinfunction "IN2+_5") (pintype "bidirectional"))
      (node (ref "R11") (pin "1") (pinfunction "1_1") (pintype "passive"))
    )
    (net (code "17") (name "Net-(COMPARATOR_2-IN2-)") (class "Default")
      (node (ref "COMPARATOR_2") (pin "6") (pinfunction "IN2-_6") (pintype "bidirectional"))
      (node (ref "R10") (pin "1") (pinfunction "1_1") (pintype "passive"))
      (node (ref "R12") (pin "2") (pinfunction "2_2") (pintype "passive"))
    )
    (net (code "18") (name "Net-(COMPARATOR_2-OUT2)") (class "Default")
      (node (ref "COMPARATOR_2") (pin "7") (pinfunction "OUT2_7") (pintype "bidirectional"))
      (node (ref "COMPARATOR_3") (pin "7") (pinfunction "OUT2_7") (pintype "bidirectional"))
      (node (ref "D_FLIP_FLOP") (pin "3") (pinfunction "1CLK_3") (pintype "bidirectional"))
      (node (ref "R16") (pin "2") (pinfunction "2_2") (pintype "passive"))
    )
    (net (code "19") (name "Net-(COMPARATOR_3-IN1-)") (class "Default")
      (node (ref "COMPARATOR_3") (pin "2") (pinfunction "IN1-_2") (pintype "bidirectional"))
      (node (ref "R40") (pin "1") (pinfunction "1_1") (pintype "passive"))
      (node (ref "R41") (pin "2") (pinfunction "2_2") (pintype "passive"))
    )
    (net (code "20") (name "Net-(COMPARATOR_3-IN2+)") (class "Default")
      (node (ref "COMPARATOR_3") (pin "5") (pinfunction "IN2+_5") (pintype "bidirectional"))
      (node (ref "R26") (pin "1") (pinfunction "1_1") (pintype "passive"))
      (node (ref "R39") (pin "2") (pinfunction "2_2") (pintype "passive"))
    )
    (net (code "21") (name "Net-(COMPARATOR_3-IN2-)") (class "Default")
      (node (ref "C14") (pin "1") (pinfunction "1_1") (pintype "passive"))
      (node (ref "COMPARATOR_3") (pin "6") (pinfunction "IN2-_6") (pintype "bidirectional"))
      (node (ref "R27") (pin "1") (pinfunction "1_1") (pintype "passive"))
    )
    (net (code "22") (name "Net-(COMPARATOR_3-OUT1)") (class "Default")
      (node (ref "COMPARATOR_3") (pin "1") (pinfunction "OUT1_1") (pintype "bidirectional"))
      (node (ref "OR") (pin "1") (pinfunction "A_1") (pintype "bidirectional"))
    )
    (net (code "23") (name "Net-(COMPARATOR_4-IN1+)") (class "Default")
      (node (ref "COMPARATOR_4") (pin "3") (pinfunction "IN1+_3") (pintype "bidirectional"))
      (node (ref "R17") (pin "1") (pinfunction "1_1") (pintype "passive"))
      (node (ref "R19") (pin "2") (pinfunction "2_2") (pintype "passive"))
    )
    (net (code "24") (name "Net-(COMPARATOR_4-IN2+)") (class "Default")
      (node (ref "COMPARATOR_4") (pin "5") (pinfunction "IN2+_5") (pintype "bidirectional"))
      (node (ref "R20") (pin "1") (pinfunction "1_1") (pintype "passive"))
      (node (ref "R22") (pin "2") (pinfunction "2_2") (pintype "passive"))
    )
    (net (code "25") (name "Net-(COMPARATOR_5-IN1+)") (class "Default")
      (node (ref "COMPARATOR_5") (pin "3") (pinfunction "IN1+_3") (pintype "bidirectional"))
      (node (ref "R18") (pin "1") (pinfunction "1_1") (pintype "passive"))
      (node (ref "R21") (pin "2") (pinfunction "2_2") (pintype "passive"))
    )
    (net (code "26") (name "Net-(COMPARATOR_5-IN2+)") (class "Default")
      (node (ref "COMPARATOR_5") (pin "5") (pinfunction "IN2+_5") (pintype "bidirectional"))
      (node (ref "R23") (pin "1") (pinfunction "1_1") (pintype "passive"))
      (node (ref "R24") (pin "2") (pinfunction "2_2") (pintype "passive"))
    )
    (net (code "27") (name "Net-(D_FLIP_FLOP-1D)") (class "Default")
      (node (ref "C11") (pin "1") (pinfunction "1_1") (pintype "passive"))
      (node (ref "D_FLIP_FLOP") (pin "1") (pinfunction "1~{CLR}_1") (pintype "bidirectional"))
      (node (ref "D_FLIP_FLOP") (pin "2") (pinfunction "1D_2") (pintype "bidirectional"))
      (node (ref "R42") (pin "1") (pinfunction "1_1") (pintype "passive"))
    )
    (net (code "28") (name "Net-(D_FLIP_FLOP-1Q)") (class "Default")
      (node (ref "D_FLIP_FLOP") (pin "5") (pinfunction "1Q_5") (pintype "bidirectional"))
      (node (ref "IMPLAUSIBILITY") (pin "1") (pinfunction "1_1") (pintype "passive"))
      (node (ref "OPTO_2") (pin "1") (pinfunction "A_1") (pintype "bidirectional"))
      (node (ref "OR") (pin "2") (pinfunction "B_2") (pintype "bidirectional"))
    )
    (net (code "29") (name "Net-(IC12-DISCH)") (class "Default")
      (node (ref "IC12") (pin "4") (pinfunction "RESET_4") (pintype "bidirectional"))
      (node (ref "IC12") (pin "7") (pinfunction "DISCH_7") (pintype "bidirectional"))
      (node (ref "R36") (pin "2") (pinfunction "2_2") (pintype "passive"))
      (node (ref "R37") (pin "1") (pinfunction "1_1") (pintype "passive"))
    )
    (net (code "30") (name "Net-(IC12-THRES)") (class "Default")
      (node (ref "C15") (pin "1") (pinfunction "1_1") (pintype "passive"))
      (node (ref "IC12") (pin "2") (pinfunction "TRIG_2") (pintype "bidirectional"))
      (node (ref "IC12") (pin "6") (pinfunction "THRES_6") (pintype "bidirectional"))
      (node (ref "R37") (pin "2") (pinfunction "2_2") (pintype "passive"))
    )
    (net (code "31") (name "Net-(NMOS_1-D)") (class "Default")
      (node (ref "NMOS_1") (pin "3") (pinfunction "D_3") (pintype "bidirectional"))
      (node (ref "OPTO_1") (pin "4") (pinfunction "D2_4") (pintype "bidirectional"))
    )
    (net (code "32") (name "Net-(NMOS_1-G)") (class "Default")
      (node (ref "NMOS_1") (pin "1") (pinfunction "G_1") (pintype "bidirectional"))
      (node (ref "R35") (pin "1") (pinfunction "1_1") (pintype "passive"))
    )
    (net (code "33") (name "Net-(NMOS_2-D)") (class "Default")
      (node (ref "NMOS_2") (pin "3") (pinfunction "D_3") (pintype "bidirectional"))
      (node (ref "OPTO_2") (pin "4") (pinfunction "D2_4") (pintype "bidirectional"))
    )
    (net (code "34") (name "Net-(NMOS_2-G)") (class "Default")
      (node (ref "NMOS_2") (pin "1") (pinfunction "G_1") (pintype "bidirectional"))
      (node (ref "R31") (pin "1") (pinfunction "1_1") (pintype "passive"))
    )
    (net (code "35") (name "Net-(OPTO_1-A)") (class "Default")
      (node (ref "OPTO_1") (pin "1") (pinfunction "A_1") (pintype "bidirectional"))
      (node (ref "OR") (pin "4") (pinfunction "Y_4") (pintype "bidirectional"))
    )
    (net (code "36") (name "Net-(OPTO_1-D1)") (class "Default")
      (node (ref "OPTO_1") (pin "3") (pinfunction "D1_3") (pintype "bidirectional"))
      (node (ref "R33") (pin "1") (pinfunction "1_1") (pintype "passive"))
      (node (ref "R34") (pin "1") (pinfunction "1_1") (pintype "passive"))
    )
    (net (code "37") (name "Net-(OPTO_1-K)") (class "Default")
      (node (ref "OPTO_1") (pin "2") (pinfunction "K_2") (pintype "bidirectional"))
      (node (ref "R32") (pin "1") (pinfunction "1_1") (pintype "passive"))
    )
    (net (code "38") (name "Net-(OPTO_2-D1)") (class "Default")
      (node (ref "OPTO_2") (pin "3") (pinfunction "D1_3") (pintype "bidirectional"))
      (node (ref "R29") (pin "1") (pinfunction "1_1") (pintype "passive"))
      (node (ref "R30") (pin "1") (pinfunction "1_1") (pintype "passive"))
    )
    (net (code "39") (name "Net-(OPTO_2-K)") (class "Default")
      (node (ref "OPTO_2") (pin "2") (pinfunction "K_2") (pintype "bidirectional"))
      (node (ref "R28") (pin "1") (pinfunction "1_1") (pintype "passive"))
    )
    (net (code "40") (name "Net-(PMOS_1-G)") (class "Default")
      (node (ref "PMOS_1") (pin "1") (pinfunction "G_1") (pintype "bidirectional"))
      (node (ref "R33") (pin "2") (pinfunction "2_2") (pintype "passive"))
    )
    (net (code "41") (name "Net-(PMOS_2-G)") (class "Default")
      (node (ref "GREEN_ON_PMOS") (pin "1") (pinfunction "1_1") (pintype "passive"))
      (node (ref "PMOS_2") (pin "1") (pinfunction "G_1") (pintype "bidirectional"))
      (node (ref "R29") (pin "2") (pinfunction "2_2") (pintype "passive"))
    )
    (net (code "42") (name "PRE_STATE") (class "Default")
      (node (ref "COMPARATOR_2") (pin "3") (pinfunction "IN1+_3") (pintype "bidirectional"))
      (node (ref "COMPARATOR_5") (pin "2") (pinfunction "IN1-_2") (pintype "bidirectional"))
      (node (ref "CONTACTOR_STATE_AND_VOLTAGE_MEASUREMENT") (pin "3") (pinfunction "S_3") (pintype "passive"))
      (node (ref "PRE_STATE") (pin "1") (pinfunction "1_1") (pintype "passive"))
      (node (ref "R8") (pin "2") (pinfunction "2_2") (pintype "passive"))
    )
    (net (code "43") (name "RED_ENABLE") (class "Default")
      (node (ref "IC12") (pin "3") (pinfunction "OUT_3") (pintype "bidirectional"))
      (node (ref "R35") (pin "2") (pinfunction "2_2") (pintype "passive"))
      (node (ref "R38") (pin "2") (pinfunction "2_2") (pintype "passive"))
      (node (ref "RED_ENABLE") (pin "1") (pinfunction "1_1") (pintype "passive"))
    )
    (net (code "44") (name "RED_ON") (class "Default")
      (node (ref "33Ω_1_") (pin "1") (pinfunction "P_1") (pintype "passive"))
      (node (ref "TSAL_LED_AND_POWER") (pin "3") (pinfunction "S_3") (pintype "passive"))
    )
    (net (code "45") (name "TS_OFF") (class "Default")
      (node (ref "680Ω_") (pin "1") (pinfunction "P_1") (pintype "passive"))
      (node (ref "TSAL_LED_AND_POWER") (pin "1") (pinfunction "S_1") (pintype "passive"))
    )
    (net (code "46") (name "VOLTAGE_ON_ACCUMULATOR") (class "Default")
      (node (ref "COMPARATOR_3") (pin "3") (pinfunction "IN1+_3") (pintype "bidirectional"))
      (node (ref "COMPARATOR_5") (pin "6") (pinfunction "IN2-_6") (pintype "bidirectional"))
      (node (ref "CONTACTOR_STATE_AND_VOLTAGE_MEASUREMENT") (pin "2") (pinfunction "S_2") (pintype "passive"))
      (node (ref "R15") (pin "2") (pinfunction "2_2") (pintype "passive"))
      (node (ref "VOLTAGE_ON_ACCUMULATOR") (pin "1") (pinfunction "1_1") (pintype "passive"))
      (node (ref "XNOR") (pin "12") (pinfunction "4A_12") (pintype "bidirectional"))
    )
    (net (code "47") (name "VOLTAGE_ON_INVERTER") (class "Default")
      (node (ref "CONTACTOR_STATE_AND_VOLTAGE_MEASUREMENT") (pin "1") (pinfunction "S_1") (pintype "passive"))
      (node (ref "R14") (pin "2") (pinfunction "2_2") (pintype "passive"))
      (node (ref "VOLTAGE_ON_INVERTER") (pin "1") (pinfunction "1_1") (pintype "passive"))
      (node (ref "XNOR") (pin "13") (pinfunction "4B_13") (pintype "bidirectional"))
    )
    (net (code "48") (name "unconnected-(D_FLIP_FLOP-1~{Q}-Pad6)") (class "Default")
      (node (ref "D_FLIP_FLOP") (pin "6") (pinfunction "1~{Q}_6") (pintype "bidirectional"))
    )
    (net (code "49") (name "unconnected-(D_FLIP_FLOP-2CLK-Pad11)") (class "Default")
      (node (ref "D_FLIP_FLOP") (pin "11") (pinfunction "2CLK_11") (pintype "bidirectional"))
    )
    (net (code "50") (name "unconnected-(D_FLIP_FLOP-2D-Pad12)") (class "Default")
      (node (ref "D_FLIP_FLOP") (pin "12") (pinfunction "2D_12") (pintype "bidirectional"))
    )
    (net (code "51") (name "unconnected-(D_FLIP_FLOP-2Q-Pad9)") (class "Default")
      (node (ref "D_FLIP_FLOP") (pin "9") (pinfunction "2Q_9") (pintype "bidirectional"))
    )
    (net (code "52") (name "unconnected-(D_FLIP_FLOP-2~{CLR}-Pad13)") (class "Default")
      (node (ref "D_FLIP_FLOP") (pin "13") (pinfunction "2~{CLR}_13") (pintype "bidirectional"))
    )
    (net (code "53") (name "unconnected-(D_FLIP_FLOP-2~{PRE}-Pad10)") (class "Default")
      (node (ref "D_FLIP_FLOP") (pin "10") (pinfunction "2~{PRE}_10") (pintype "bidirectional"))
    )
    (net (code "54") (name "unconnected-(D_FLIP_FLOP-2~{Q}-Pad8)") (class "Default")
      (node (ref "D_FLIP_FLOP") (pin "8") (pinfunction "2~{Q}_8") (pintype "bidirectional"))
    )
    (net (code "55") (name "unconnected-(IC12-CONT-Pad5)") (class "Default")
      (node (ref "IC12") (pin "5") (pinfunction "CONT_5") (pintype "bidirectional"))
    )
    (net (code "56") (name "unconnected-(XNOR-1A-Pad1)") (class "Default")
      (node (ref "XNOR") (pin "1") (pinfunction "1A_1") (pintype "bidirectional"))
    )
    (net (code "57") (name "unconnected-(XNOR-1B-Pad2)") (class "Default")
      (node (ref "XNOR") (pin "2") (pinfunction "1B_2") (pintype "bidirectional"))
    )
    (net (code "58") (name "unconnected-(XNOR-1Y-Pad3)") (class "Default")
      (node (ref "XNOR") (pin "3") (pinfunction "1Y_3") (pintype "bidirectional"))
    )
    (net (code "59") (name "unconnected-(XNOR-2A-Pad5)") (class "Default")
      (node (ref "XNOR") (pin "5") (pinfunction "2A_5") (pintype "bidirectional"))
    )
    (net (code "60") (name "unconnected-(XNOR-2B-Pad6)") (class "Default")
      (node (ref "XNOR") (pin "6") (pinfunction "2B_6") (pintype "bidirectional"))
    )
    (net (code "61") (name "unconnected-(XNOR-2Y-Pad4)") (class "Default")
      (node (ref "XNOR") (pin "4") (pinfunction "2Y_4") (pintype "bidirectional"))
    )
    (net (code "62") (name "unconnected-(XNOR-3A-Pad8)") (class "Default")
      (node (ref "XNOR") (pin "8") (pinfunction "3A_8") (pintype "bidirectional"))
    )
    (net (code "63") (name "unconnected-(XNOR-3B-Pad9)") (class "Default")
      (node (ref "XNOR") (pin "9") (pinfunction "3B_9") (pintype "bidirectional"))
    )
    (net (code "64") (name "unconnected-(XNOR-3Y-Pad10)") (class "Default")
      (node (ref "XNOR") (pin "10") (pinfunction "3Y_10") (pintype "bidirectional"))
    )
  )
)
